# PWM.net
KiCad netlist of a schematic drawn in Altium Designer
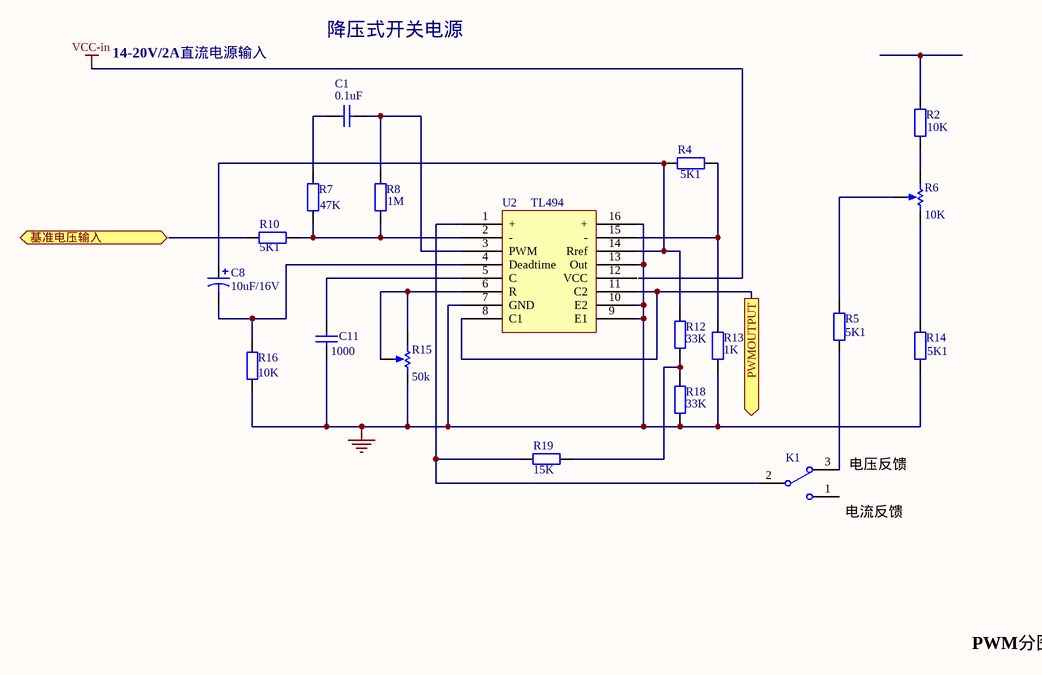
[diagram p0: PWM分图.SchDoc]

(export (version "E")
  (design (tool "Eeschema 10.0.6"))
  (components
    (comp (ref "C1")
      (value "0.1uF")
      (footprint "Cap")
      (description "Capacitor")
      (fields (field (name "Comment") "Cap") (field (name "PUBLISHER") "Altium Limited"))
      (libsource (lib "Miscellaneous Devices") (part "Cap"))
    )
    (comp (ref "C8")
      (value "10uF/16V")
      (footprint "RB7.6-15")
      (description "Polarized Capacitor (Radial)")
      (fields (field (name "Comment") "Cap Pol1") (field (name "PUBLISHER") "Altium Limited"))
      (libsource (lib "Miscellaneous Devices") (part "Cap Pol1"))
    )
    (comp (ref "C11")
      (value "1000")
      (footprint "Cap")
      (description "Capacitor")
      (fields (field (name "Comment") "Cap") (field (name "PUBLISHER") "Altium Limited"))
      (libsource (lib "Miscellaneous Devices") (part "Cap"))
    )
    (comp (ref "K1")
      (value "SW-SPDT")
      (footprint "TL36WW15050")
      (description "SPDT Subminiature Toggle Switch, Right Angle Mounting, Vertical Actuation")
      (fields (field (name "PUBLISHER") "Altium Limited"))
      (libsource (lib "Miscellaneous Devices") (part "SW-SPDT"))
    )
    (comp (ref "R2")
      (value "10K")
      (footprint "AXIAL-0.4")
      (description "Resistor")
      (fields (field (name "Comment") "Res2") (field (name "PUBLISHER") "Altium Limited"))
      (libsource (lib "Miscellaneous Devices") (part "Res2"))
    )
    (comp (ref "R4")
      (value "5K1")
      (footprint "AXIAL-0.4")
      (description "Resistor")
      (fields (field (name "Comment") "Res2") (field (name "PUBLISHER") "Altium Limited"))
      (libsource (lib "") (part "Res2_1"))
    )
    (comp (ref "R5")
      (value "5K1")
      (footprint "AXIAL-0.4")
      (description "Resistor")
      (fields (field (name "Comment") "Res2") (field (name "PUBLISHER") "Altium Limited"))
      (libsource (lib "Miscellaneous Devices") (part "Res2"))
    )
    (comp (ref "R6")
      (value "10K")
      (footprint "VR5")
      (description "Potentiometer")
      (fields (field (name "Comment") "RPot") (field (name "PUBLISHER") "Altium Limited"))
      (libsource (lib "Miscellaneous Devices") (part "RPot"))
    )
    (comp (ref "R7")
      (value "47K")
      (footprint "AXIAL-0.4")
      (description "Resistor")
      (fields (field (name "Comment") "Res2") (field (name "PUBLISHER") "Altium Limited"))
      (libsource (lib "Miscellaneous Devices") (part "Res2"))
    )
    (comp (ref "R8")
      (value "1M")
      (footprint "AXIAL-0.4")
      (description "Resistor")
      (fields (field (name "Comment") "Res2") (field (name "PUBLISHER") "Altium Limited"))
      (libsource (lib "Miscellaneous Devices") (part "Res2"))
    )
    (comp (ref "R10")
      (value "5K1")
      (footprint "AXIAL-0.4")
      (description "Resistor")
      (fields (field (name "Comment") "Res2") (field (name "PUBLISHER") "Altium Limited"))
      (libsource (lib "") (part "Res2_1"))
    )
    (comp (ref "R12")
      (value "33K")
      (footprint "AXIAL-0.4")
      (description "Resistor")
      (fields (field (name "Comment") "Res2") (field (name "PUBLISHER") "Altium Limited"))
      (libsource (lib "Miscellaneous Devices") (part "Res2"))
    )
    (comp (ref "R13")
      (value "1K")
      (footprint "AXIAL-0.4")
      (description "Resistor")
      (fields (field (name "Comment") "Res2") (field (name "PUBLISHER") "Altium Limited"))
      (libsource (lib "Miscellaneous Devices") (part "Res2"))
    )
    (comp (ref "R14")
      (value "5K1")
      (footprint "AXIAL-0.4")
      (description "Resistor")
      (fields (field (name "Comment") "Res2") (field (name "PUBLISHER") "Altium Limited"))
      (libsource (lib "Miscellaneous Devices") (part "Res2"))
    )
    (comp (ref "R15")
      (value "50k")
      (footprint "VR5")
      (description "Potentiometer")
      (fields (field (name "Comment") "RPot") (field (name "PUBLISHER") "Altium Limited"))
      (libsource (lib "Miscellaneous Devices") (part "RPot"))
    )
    (comp (ref "R16")
      (value "10K")
      (footprint "AXIAL-0.4")
      (description "Resistor")
      (fields (field (name "Comment") "Res2") (field (name "PUBLISHER") "Altium Limited"))
      (libsource (lib "Miscellaneous Devices") (part "Res2"))
    )
    (comp (ref "R18")
      (value "33K")
      (footprint "AXIAL-0.4")
      (description "Resistor")
      (fields (field (name "Comment") "Res2") (field (name "PUBLISHER") "Altium Limited"))
      (libsource (lib "Miscellaneous Devices") (part "Res2"))
    )
    (comp (ref "R19")
      (value "15K")
      (footprint "AXIAL-0.4")
      (description "Resistor")
      (fields (field (name "Comment") "Res2") (field (name "PUBLISHER") "Altium Limited"))
      (libsource (lib "") (part "Res2_2"))
    )
    (comp (ref "U2") (value "TL494") (footprint "DIP16") (libsource (lib "Tl494") (part "Tl494")))
  )
  (nets
    (net (code "1") (name "/PWMOUTPUT") (class "Default")
      (node (ref "U2") (pin "11") (pinfunction "C2_11") (pintype "passive"))
      (node (ref "U2") (pin "8") (pinfunction "C1_8") (pintype "passive"))
    )
    (net (code "3") (name "GND") (class "Default")
      (node (ref "C11") (pin "1") (pinfunction "1_1") (pintype "passive"))
      (node (ref "R13") (pin "1") (pinfunction "1_1") (pintype "passive"))
      (node (ref "R14") (pin "1") (pinfunction "1_1") (pintype "passive"))
      (node (ref "R15") (pin "2") (pinfunction "BOT_2") (pintype "passive"))
      (node (ref "R16") (pin "1") (pinfunction "1_1") (pintype "passive"))
      (node (ref "R18") (pin "1") (pinfunction "1_1") (pintype "passive"))
      (node (ref "U2") (pin "10") (pinfunction "E2_10") (pintype "passive"))
      (node (ref "U2") (pin "13") (pinfunction "Out_13") (pintype "passive"))
      (node (ref "U2") (pin "16") (pinfunction "+_16") (pintype "passive"))
      (node (ref "U2") (pin "7") (pinfunction "GND_7") (pintype "passive"))
      (node (ref "U2") (pin "9") (pinfunction "E1_9") (pintype "passive"))
    )
    (net (code "4") (name "Net-(C1-Pad2)") (class "Default")
      (node (ref "C1") (pin "2") (pinfunction "2_2") (pintype "passive"))
      (node (ref "R7") (pin "2") (pinfunction "2_2") (pintype "passive"))
    )
    (net (code "5") (name "Net-(K1-Pad2)") (class "Default")
      (node (ref "K1") (pin "2") (pinfunction "2_2") (pintype "passive"))
      (node (ref "R19") (pin "2") (pinfunction "2_2") (pintype "passive"))
      (node (ref "U2") (pin "1") (pinfunction "+_1") (pintype "passive"))
    )
    (net (code "6") (name "Net-(K1-Pad3)") (class "Default")
      (node (ref "K1") (pin "3") (pinfunction "3_3") (pintype "passive"))
      (node (ref "R5") (pin "1") (pinfunction "1_1") (pintype "passive"))
    )
    (net (code "7") (name "Net-(R6-BOT)") (class "Default")
      (node (ref "R14") (pin "2") (pinfunction "2_2") (pintype "passive"))
      (node (ref "R6") (pin "2") (pinfunction "BOT_2") (pintype "passive"))
    )
    (net (code "8") (name "Net-(R6-TAP)") (class "Default")
      (node (ref "R5") (pin "2") (pinfunction "2_2") (pintype "passive"))
      (node (ref "R6") (pin "3") (pinfunction "TAP_3") (pintype "passive"))
    )
    (net (code "9") (name "Net-(R6-TOP)") (class "Default")
      (node (ref "R2") (pin "1") (pinfunction "1_1") (pintype "passive"))
      (node (ref "R6") (pin "1") (pinfunction "TOP_1") (pintype "passive"))
    )
    (net (code "10") (name "Net-(R10-Pad2)") (class "Default")
      (node (ref "R10") (pin "2") (pinfunction "2_2") (pintype "passive"))
      (node (ref "R7") (pin "1") (pinfunction "1_1") (pintype "passive"))
      (node (ref "R8") (pin "1") (pinfunction "1_1") (pintype "passive"))
      (node (ref "U2") (pin "2") (pinfunction "-_2") (pintype "passive"))
    )
    (net (code "11") (name "Net-(R12-Pad1)") (class "Default")
      (node (ref "R12") (pin "1") (pinfunction "1_1") (pintype "passive"))
      (node (ref "R18") (pin "2") (pinfunction "2_2") (pintype "passive"))
      (node (ref "R19") (pin "1") (pinfunction "1_1") (pintype "passive"))
    )
    (net (code "12") (name "Net-(R13-Pad2)") (class "Default")
      (node (ref "R13") (pin "2") (pinfunction "2_2") (pintype "passive"))
      (node (ref "R4") (pin "2") (pinfunction "2_2") (pintype "passive"))
      (node (ref "U2") (pin "15") (pinfunction "-_15") (pintype "passive"))
    )
    (net (code "13") (name "Net-(R15-TAP)") (class "Default")
      (node (ref "R15") (pin "1") (pinfunction "TOP_1") (pintype "passive"))
      (node (ref "R15") (pin "3") (pinfunction "TAP_3") (pintype "passive"))
      (node (ref "U2") (pin "6") (pinfunction "R_6") (pintype "passive"))
    )
    (net (code "14") (name "Net-(U2-C)") (class "Default")
      (node (ref "C11") (pin "2") (pinfunction "2_2") (pintype "passive"))
      (node (ref "U2") (pin "5") (pinfunction "C_5") (pintype "passive"))
    )
    (net (code "15") (name "Net-(U2-Deadtime)") (class "Default")
      (node (ref "C8") (pin "2") (pinfunction "2_2") (pintype "passive"))
      (node (ref "R16") (pin "2") (pinfunction "2_2") (pintype "passive"))
      (node (ref "U2") (pin "4") (pinfunction "Deadtime_4") (pintype "passive"))
    )
    (net (code "16") (name "Net-(U2-PWM)") (class "Default")
      (node (ref "C1") (pin "1") (pinfunction "1_1") (pintype "passive"))
      (node (ref "R8") (pin "2") (pinfunction "2_2") (pintype "passive"))
      (node (ref "U2") (pin "3") (pinfunction "PWM_3") (pintype "passive"))
    )
    (net (code "17") (name "Net-(U2-Rref)") (class "Default")
      (node (ref "C8") (pin "1") (pinfunction "1_1") (pintype "passive"))
      (node (ref "R12") (pin "2") (pinfunction "2_2") (pintype "passive"))
      (node (ref "R4") (pin "1") (pinfunction "1_1") (pintype "passive"))
      (node (ref "U2") (pin "14") (pinfunction "Rref_14") (pintype "passive"))
    )
    (net (code "19") (name "unconnected-(K1-Pad1)") (class "Default")
      (node (ref "K1") (pin "1") (pinfunction "1_1") (pintype "passive"))
    )
    (net (code "20") (name "unconnected-(R2-Pad2)") (class "Default")
      (node (ref "R2") (pin "2") (pinfunction "2_2") (pintype "passive"))
    )
    (net (code "21") (name "unconnected-(R10-Pad1)") (class "Default")
      (node (ref "R10") (pin "1") (pinfunction "1_1") (pintype "passive"))
    )
    (net (code "22") (name "unconnected-(U2-VCC-Pad12)") (class "Default")
      (node (ref "U2") (pin "12") (pinfunction "VCC_12") (pintype "passive"))
    )
  )
)
